# relays1.net
KiCad netlist of a schematic drawn in Altium Designer
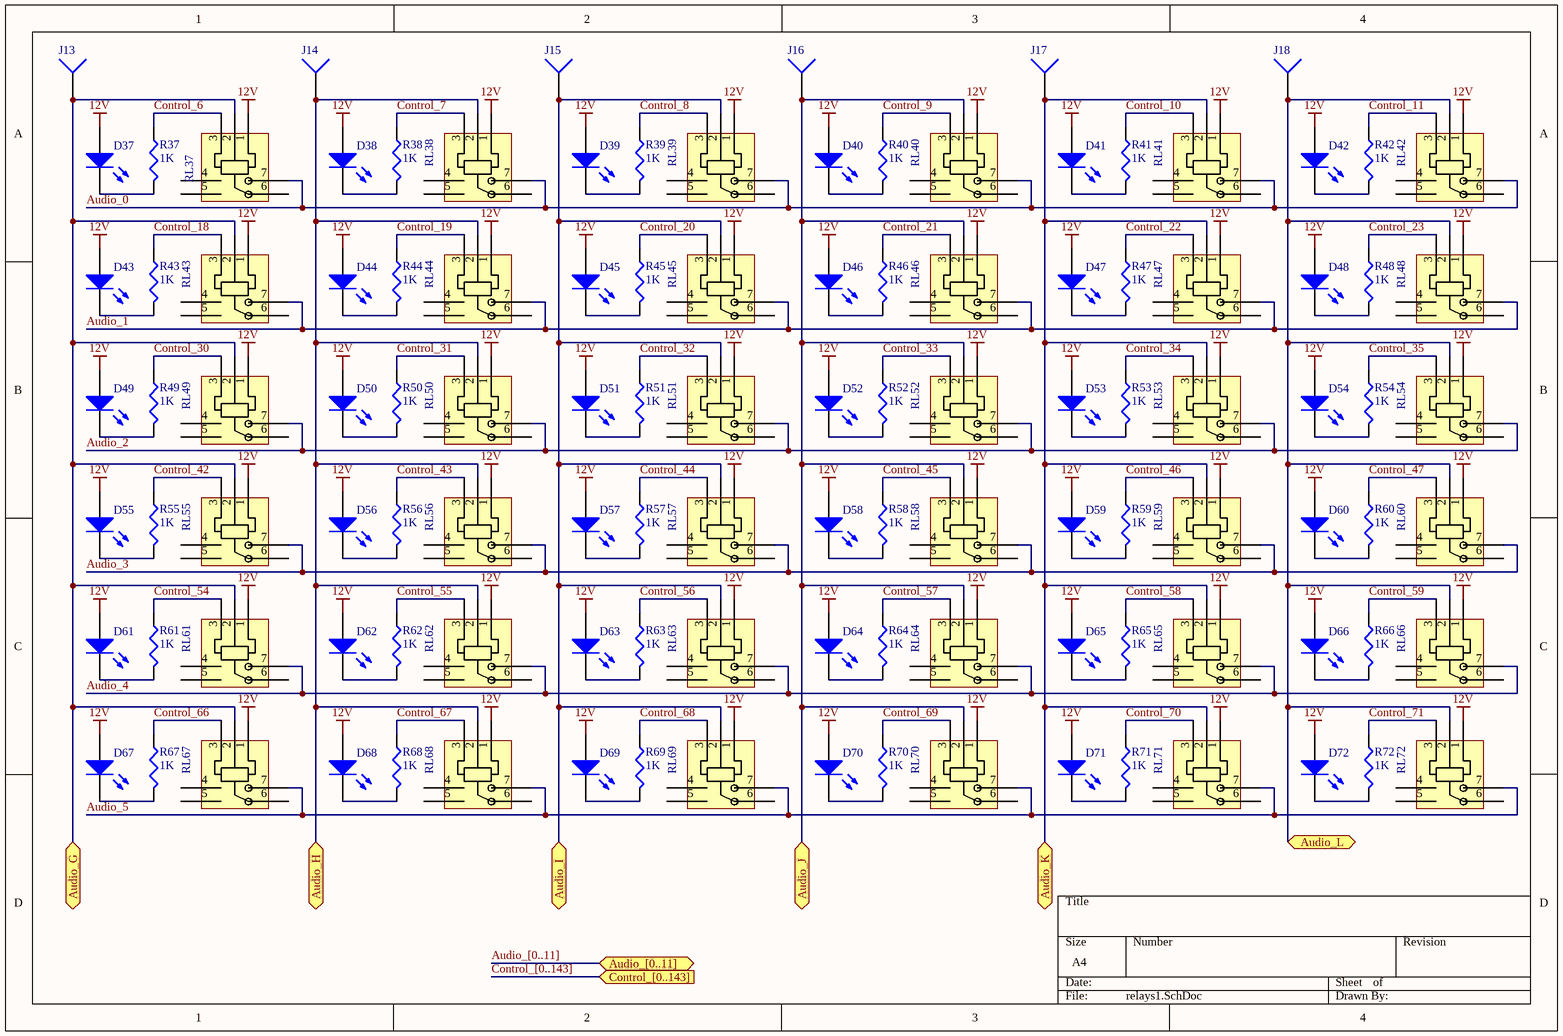
[diagram p0: relays1.SchDoc]

(export (version "E")
  (design (tool "Eeschema 10.0.6"))
  (components
    (comp (ref "D37")
      (value "LED0")
      (footprint "LED_round_5mm")
      (description "Typical INFRARED GaAs LED")
      (libsource (lib "Miscellaneous Devices") (part "LED0"))
    )
    (comp (ref "D38")
      (value "LED0")
      (footprint "LED_round_5mm")
      (description "Typical INFRARED GaAs LED")
      (libsource (lib "Miscellaneous Devices") (part "LED0"))
    )
    (comp (ref "D39")
      (value "LED0")
      (footprint "LED_round_5mm")
      (description "Typical INFRARED GaAs LED")
      (libsource (lib "Miscellaneous Devices") (part "LED0"))
    )
    (comp (ref "D40")
      (value "LED0")
      (footprint "LED_round_5mm")
      (description "Typical INFRARED GaAs LED")
      (libsource (lib "Miscellaneous Devices") (part "LED0"))
    )
    (comp (ref "D41")
      (value "LED0")
      (footprint "LED_round_5mm")
      (description "Typical INFRARED GaAs LED")
      (libsource (lib "Miscellaneous Devices") (part "LED0"))
    )
    (comp (ref "D42")
      (value "LED0")
      (footprint "LED_round_5mm")
      (description "Typical INFRARED GaAs LED")
      (libsource (lib "Miscellaneous Devices") (part "LED0"))
    )
    (comp (ref "D43")
      (value "LED0")
      (footprint "LED_round_5mm")
      (description "Typical INFRARED GaAs LED")
      (libsource (lib "Miscellaneous Devices") (part "LED0"))
    )
    (comp (ref "D44")
      (value "LED0")
      (footprint "LED_round_5mm")
      (description "Typical INFRARED GaAs LED")
      (libsource (lib "Miscellaneous Devices") (part "LED0"))
    )
    (comp (ref "D45")
      (value "LED0")
      (footprint "LED_round_5mm")
      (description "Typical INFRARED GaAs LED")
      (libsource (lib "Miscellaneous Devices") (part "LED0"))
    )
    (comp (ref "D46")
      (value "LED0")
      (footprint "LED_round_5mm")
      (description "Typical INFRARED GaAs LED")
      (libsource (lib "Miscellaneous Devices") (part "LED0"))
    )
    (comp (ref "D47")
      (value "LED0")
      (footprint "LED_round_5mm")
      (description "Typical INFRARED GaAs LED")
      (libsource (lib "Miscellaneous Devices") (part "LED0"))
    )
    (comp (ref "D48")
      (value "LED0")
      (footprint "LED_round_5mm")
      (description "Typical INFRARED GaAs LED")
      (libsource (lib "Miscellaneous Devices") (part "LED0"))
    )
    (comp (ref "D49")
      (value "LED0")
      (footprint "LED_round_5mm")
      (description "Typical INFRARED GaAs LED")
      (libsource (lib "Miscellaneous Devices") (part "LED0"))
    )
    (comp (ref "D50")
      (value "LED0")
      (footprint "LED_round_5mm")
      (description "Typical INFRARED GaAs LED")
      (libsource (lib "Miscellaneous Devices") (part "LED0"))
    )
    (comp (ref "D51")
      (value "LED0")
      (footprint "LED_round_5mm")
      (description "Typical INFRARED GaAs LED")
      (libsource (lib "Miscellaneous Devices") (part "LED0"))
    )
    (comp (ref "D52")
      (value "LED0")
      (footprint "LED_round_5mm")
      (description "Typical INFRARED GaAs LED")
      (libsource (lib "Miscellaneous Devices") (part "LED0"))
    )
    (comp (ref "D53")
      (value "LED0")
      (footprint "LED_round_5mm")
      (description "Typical INFRARED GaAs LED")
      (libsource (lib "Miscellaneous Devices") (part "LED0"))
    )
    (comp (ref "D54")
      (value "LED0")
      (footprint "LED_round_5mm")
      (description "Typical INFRARED GaAs LED")
      (libsource (lib "Miscellaneous Devices") (part "LED0"))
    )
    (comp (ref "D55")
      (value "LED0")
      (footprint "LED_round_5mm")
      (description "Typical INFRARED GaAs LED")
      (libsource (lib "Miscellaneous Devices") (part "LED0"))
    )
    (comp (ref "D56")
      (value "LED0")
      (footprint "LED_round_5mm")
      (description "Typical INFRARED GaAs LED")
      (libsource (lib "Miscellaneous Devices") (part "LED0"))
    )
    (comp (ref "D57")
      (value "LED0")
      (footprint "LED_round_5mm")
      (description "Typical INFRARED GaAs LED")
      (libsource (lib "Miscellaneous Devices") (part "LED0"))
    )
    (comp (ref "D58")
      (value "LED0")
      (footprint "LED_round_5mm")
      (description "Typical INFRARED GaAs LED")
      (libsource (lib "Miscellaneous Devices") (part "LED0"))
    )
    (comp (ref "D59")
      (value "LED0")
      (footprint "LED_round_5mm")
      (description "Typical INFRARED GaAs LED")
      (libsource (lib "Miscellaneous Devices") (part "LED0"))
    )
    (comp (ref "D60")
      (value "LED0")
      (footprint "LED_round_5mm")
      (description "Typical INFRARED GaAs LED")
      (libsource (lib "Miscellaneous Devices") (part "LED0"))
    )
    (comp (ref "D61")
      (value "LED0")
      (footprint "LED_round_5mm")
      (description "Typical INFRARED GaAs LED")
      (libsource (lib "Miscellaneous Devices") (part "LED0"))
    )
    (comp (ref "D62")
      (value "LED0")
      (footprint "LED_round_5mm")
      (description "Typical INFRARED GaAs LED")
      (libsource (lib "Miscellaneous Devices") (part "LED0"))
    )
    (comp (ref "D63")
      (value "LED0")
      (footprint "LED_round_5mm")
      (description "Typical INFRARED GaAs LED")
      (libsource (lib "Miscellaneous Devices") (part "LED0"))
    )
    (comp (ref "D64")
      (value "LED0")
      (footprint "LED_round_5mm")
      (description "Typical INFRARED GaAs LED")
      (libsource (lib "Miscellaneous Devices") (part "LED0"))
    )
    (comp (ref "D65")
      (value "LED0")
      (footprint "LED_round_5mm")
      (description "Typical INFRARED GaAs LED")
      (libsource (lib "Miscellaneous Devices") (part "LED0"))
    )
    (comp (ref "D66")
      (value "LED0")
      (footprint "LED_round_5mm")
      (description "Typical INFRARED GaAs LED")
      (libsource (lib "Miscellaneous Devices") (part "LED0"))
    )
    (comp (ref "D67")
      (value "LED0")
      (footprint "LED_round_5mm")
      (description "Typical INFRARED GaAs LED")
      (libsource (lib "Miscellaneous Devices") (part "LED0"))
    )
    (comp (ref "D68")
      (value "LED0")
      (footprint "LED_round_5mm")
      (description "Typical INFRARED GaAs LED")
      (libsource (lib "Miscellaneous Devices") (part "LED0"))
    )
    (comp (ref "D69")
      (value "LED0")
      (footprint "LED_round_5mm")
      (description "Typical INFRARED GaAs LED")
      (libsource (lib "Miscellaneous Devices") (part "LED0"))
    )
    (comp (ref "D70")
      (value "LED0")
      (footprint "LED_round_5mm")
      (description "Typical INFRARED GaAs LED")
      (libsource (lib "Miscellaneous Devices") (part "LED0"))
    )
    (comp (ref "D71")
      (value "LED0")
      (footprint "LED_round_5mm")
      (description "Typical INFRARED GaAs LED")
      (libsource (lib "Miscellaneous Devices") (part "LED0"))
    )
    (comp (ref "D72")
      (value "LED0")
      (footprint "LED_round_5mm")
      (description "Typical INFRARED GaAs LED")
      (libsource (lib "Miscellaneous Devices") (part "LED0"))
    )
    (comp (ref "J13")
      (value "Audio")
      (footprint "Conn_1_2x4")
      (description "Socket")
      (libsource (lib "Miscellaneous Connectors") (part "Socket"))
    )
    (comp (ref "J14")
      (value "Audio")
      (footprint "Conn_1_2x4")
      (description "Socket")
      (libsource (lib "Miscellaneous Connectors") (part "Socket"))
    )
    (comp (ref "J15")
      (value "Audio")
      (footprint "Conn_1_2x4")
      (description "Socket")
      (libsource (lib "Miscellaneous Connectors") (part "Socket"))
    )
    (comp (ref "J16")
      (value "Audio")
      (footprint "Conn_1_2x4")
      (description "Socket")
      (libsource (lib "Miscellaneous Connectors") (part "Socket"))
    )
    (comp (ref "J17")
      (value "Audio")
      (footprint "Conn_1_2x4")
      (description "Socket")
      (libsource (lib "Miscellaneous Connectors") (part "Socket"))
    )
    (comp (ref "J18")
      (value "Audio")
      (footprint "Conn_1_2x4")
      (description "Socket")
      (libsource (lib "Miscellaneous Connectors") (part "Socket"))
    )
    (comp (ref "R37")
      (value "1K")
      (footprint "J1-0603")
      (description "Resistor")
      (fields (field (name "Comment") "Res3"))
      (libsource (lib "Miscellaneous Devices") (part "Res3"))
    )
    (comp (ref "R38")
      (value "1K")
      (footprint "J1-0603")
      (description "Resistor")
      (fields (field (name "Comment") "Res3"))
      (libsource (lib "Miscellaneous Devices") (part "Res3"))
    )
    (comp (ref "R39")
      (value "1K")
      (footprint "J1-0603")
      (description "Resistor")
      (fields (field (name "Comment") "Res3"))
      (libsource (lib "Miscellaneous Devices") (part "Res3"))
    )
    (comp (ref "R40")
      (value "1K")
      (footprint "J1-0603")
      (description "Resistor")
      (fields (field (name "Comment") "Res3"))
      (libsource (lib "Miscellaneous Devices") (part "Res3"))
    )
    (comp (ref "R41")
      (value "1K")
      (footprint "J1-0603")
      (description "Resistor")
      (fields (field (name "Comment") "Res3"))
      (libsource (lib "Miscellaneous Devices") (part "Res3"))
    )
    (comp (ref "R42")
      (value "1K")
      (footprint "J1-0603")
      (description "Resistor")
      (fields (field (name "Comment") "Res3"))
      (libsource (lib "Miscellaneous Devices") (part "Res3"))
    )
    (comp (ref "R43")
      (value "1K")
      (footprint "J1-0603")
      (description "Resistor")
      (fields (field (name "Comment") "Res3"))
      (libsource (lib "Miscellaneous Devices") (part "Res3"))
    )
    (comp (ref "R44")
      (value "1K")
      (footprint "J1-0603")
      (description "Resistor")
      (fields (field (name "Comment") "Res3"))
      (libsource (lib "Miscellaneous Devices") (part "Res3"))
    )
    (comp (ref "R45")
      (value "1K")
      (footprint "J1-0603")
      (description "Resistor")
      (fields (field (name "Comment") "Res3"))
      (libsource (lib "Miscellaneous Devices") (part "Res3"))
    )
    (comp (ref "R46")
      (value "1K")
      (footprint "J1-0603")
      (description "Resistor")
      (fields (field (name "Comment") "Res3"))
      (libsource (lib "Miscellaneous Devices") (part "Res3"))
    )
    (comp (ref "R47")
      (value "1K")
      (footprint "J1-0603")
      (description "Resistor")
      (fields (field (name "Comment") "Res3"))
      (libsource (lib "Miscellaneous Devices") (part "Res3"))
    )
    (comp (ref "R48")
      (value "1K")
      (footprint "J1-0603")
      (description "Resistor")
      (fields (field (name "Comment") "Res3"))
      (libsource (lib "Miscellaneous Devices") (part "Res3"))
    )
    (comp (ref "R49")
      (value "1K")
      (footprint "J1-0603")
      (description "Resistor")
      (fields (field (name "Comment") "Res3"))
      (libsource (lib "Miscellaneous Devices") (part "Res3"))
    )
    (comp (ref "R50")
      (value "1K")
      (footprint "J1-0603")
      (description "Resistor")
      (fields (field (name "Comment") "Res3"))
      (libsource (lib "Miscellaneous Devices") (part "Res3"))
    )
    (comp (ref "R51")
      (value "1K")
      (footprint "J1-0603")
      (description "Resistor")
      (fields (field (name "Comment") "Res3"))
      (libsource (lib "Miscellaneous Devices") (part "Res3"))
    )
    (comp (ref "R52")
      (value "1K")
      (footprint "J1-0603")
      (description "Resistor")
      (fields (field (name "Comment") "Res3"))
      (libsource (lib "Miscellaneous Devices") (part "Res3"))
    )
    (comp (ref "R53")
      (value "1K")
      (footprint "J1-0603")
      (description "Resistor")
      (fields (field (name "Comment") "Res3"))
      (libsource (lib "Miscellaneous Devices") (part "Res3"))
    )
    (comp (ref "R54")
      (value "1K")
      (footprint "J1-0603")
      (description "Resistor")
      (fields (field (name "Comment") "Res3"))
      (libsource (lib "Miscellaneous Devices") (part "Res3"))
    )
    (comp (ref "R55")
      (value "1K")
      (footprint "J1-0603")
      (description "Resistor")
      (fields (field (name "Comment") "Res3"))
      (libsource (lib "Miscellaneous Devices") (part "Res3"))
    )
    (comp (ref "R56")
      (value "1K")
      (footprint "J1-0603")
      (description "Resistor")
      (fields (field (name "Comment") "Res3"))
      (libsource (lib "Miscellaneous Devices") (part "Res3"))
    )
    (comp (ref "R57")
      (value "1K")
      (footprint "J1-0603")
      (description "Resistor")
      (fields (field (name "Comment") "Res3"))
      (libsource (lib "Miscellaneous Devices") (part "Res3"))
    )
    (comp (ref "R58")
      (value "1K")
      (footprint "J1-0603")
      (description "Resistor")
      (fields (field (name "Comment") "Res3"))
      (libsource (lib "Miscellaneous Devices") (part "Res3"))
    )
    (comp (ref "R59")
      (value "1K")
      (footprint "J1-0603")
      (description "Resistor")
      (fields (field (name "Comment") "Res3"))
      (libsource (lib "Miscellaneous Devices") (part "Res3"))
    )
    (comp (ref "R60")
      (value "1K")
      (footprint "J1-0603")
      (description "Resistor")
      (fields (field (name "Comment") "Res3"))
      (libsource (lib "Miscellaneous Devices") (part "Res3"))
    )
    (comp (ref "R61")
      (value "1K")
      (footprint "J1-0603")
      (description "Resistor")
      (fields (field (name "Comment") "Res3"))
      (libsource (lib "Miscellaneous Devices") (part "Res3"))
    )
    (comp (ref "R62")
      (value "1K")
      (footprint "J1-0603")
      (description "Resistor")
      (fields (field (name "Comment") "Res3"))
      (libsource (lib "Miscellaneous Devices") (part "Res3"))
    )
    (comp (ref "R63")
      (value "1K")
      (footprint "J1-0603")
      (description "Resistor")
      (fields (field (name "Comment") "Res3"))
      (libsource (lib "Miscellaneous Devices") (part "Res3"))
    )
    (comp (ref "R64")
      (value "1K")
      (footprint "J1-0603")
      (description "Resistor")
      (fields (field (name "Comment") "Res3"))
      (libsource (lib "Miscellaneous Devices") (part "Res3"))
    )
    (comp (ref "R65")
      (value "1K")
      (footprint "J1-0603")
      (description "Resistor")
      (fields (field (name "Comment") "Res3"))
      (libsource (lib "Miscellaneous Devices") (part "Res3"))
    )
    (comp (ref "R66")
      (value "1K")
      (footprint "J1-0603")
      (description "Resistor")
      (fields (field (name "Comment") "Res3"))
      (libsource (lib "Miscellaneous Devices") (part "Res3"))
    )
    (comp (ref "R67")
      (value "1K")
      (footprint "J1-0603")
      (description "Resistor")
      (fields (field (name "Comment") "Res3"))
      (libsource (lib "Miscellaneous Devices") (part "Res3"))
    )
    (comp (ref "R68")
      (value "1K")
      (footprint "J1-0603")
      (description "Resistor")
      (fields (field (name "Comment") "Res3"))
      (libsource (lib "Miscellaneous Devices") (part "Res3"))
    )
    (comp (ref "R69")
      (value "1K")
      (footprint "J1-0603")
      (description "Resistor")
      (fields (field (name "Comment") "Res3"))
      (libsource (lib "Miscellaneous Devices") (part "Res3"))
    )
    (comp (ref "R70")
      (value "1K")
      (footprint "J1-0603")
      (description "Resistor")
      (fields (field (name "Comment") "Res3"))
      (libsource (lib "Miscellaneous Devices") (part "Res3"))
    )
    (comp (ref "R71")
      (value "1K")
      (footprint "J1-0603")
      (description "Resistor")
      (fields (field (name "Comment") "Res3"))
      (libsource (lib "Miscellaneous Devices") (part "Res3"))
    )
    (comp (ref "R72")
      (value "1K")
      (footprint "J1-0603")
      (description "Resistor")
      (fields (field (name "Comment") "Res3"))
      (libsource (lib "Miscellaneous Devices") (part "Res3"))
    )
    (comp (ref "RL37")
      (value "Relay")
      (footprint "Relay_FRA3")
      (description "Miniature power relay")
      (fields (field (name "PART NUMBER") "FRA3C-DC12"))
      (libsource (lib "tech-thing") (part "Relay_FRA3"))
    )
    (comp (ref "RL38")
      (value "Relay")
      (footprint "Relay_FRA3")
      (description "Miniature power relay")
      (fields (field (name "PART NUMBER") "FRA3C-DC12"))
      (libsource (lib "tech-thing") (part "Relay_FRA3"))
    )
    (comp (ref "RL39")
      (value "Relay")
      (footprint "Relay_FRA3")
      (description "Miniature power relay")
      (fields (field (name "PART NUMBER") "FRA3C-DC12"))
      (libsource (lib "tech-thing") (part "Relay_FRA3"))
    )
    (comp (ref "RL40")
      (value "Relay")
      (footprint "Relay_FRA3")
      (description "Miniature power relay")
      (fields (field (name "PART NUMBER") "FRA3C-DC12"))
      (libsource (lib "tech-thing") (part "Relay_FRA3"))
    )
    (comp (ref "RL41")
      (value "Relay")
      (footprint "Relay_FRA3")
      (description "Miniature power relay")
      (fields (field (name "PART NUMBER") "FRA3C-DC12"))
      (libsource (lib "tech-thing") (part "Relay_FRA3"))
    )
    (comp (ref "RL42")
      (value "Relay")
      (footprint "Relay_FRA3")
      (description "Miniature power relay")
      (fields (field (name "PART NUMBER") "FRA3C-DC12"))
      (libsource (lib "tech-thing") (part "Relay_FRA3"))
    )
    (comp (ref "RL43")
      (value "Relay")
      (footprint "Relay_FRA3")
      (description "Miniature power relay")
      (fields (field (name "PART NUMBER") "FRA3C-DC12"))
      (libsource (lib "tech-thing") (part "Relay_FRA3"))
    )
    (comp (ref "RL44")
      (value "Relay")
      (footprint "Relay_FRA3")
      (description "Miniature power relay")
      (fields (field (name "PART NUMBER") "FRA3C-DC12"))
      (libsource (lib "tech-thing") (part "Relay_FRA3"))
    )
    (comp (ref "RL45")
      (value "Relay")
      (footprint "Relay_FRA3")
      (description "Miniature power relay")
      (fields (field (name "PART NUMBER") "FRA3C-DC12"))
      (libsource (lib "tech-thing") (part "Relay_FRA3"))
    )
    (comp (ref "RL46")
      (value "Relay")
      (footprint "Relay_FRA3")
      (description "Miniature power relay")
      (fields (field (name "PART NUMBER") "FRA3C-DC12"))
      (libsource (lib "tech-thing") (part "Relay_FRA3"))
    )
    (comp (ref "RL47")
      (value "Relay")
      (footprint "Relay_FRA3")
      (description "Miniature power relay")
      (fields (field (name "PART NUMBER") "FRA3C-DC12"))
      (libsource (lib "tech-thing") (part "Relay_FRA3"))
    )
    (comp (ref "RL48")
      (value "Relay")
      (footprint "Relay_FRA3")
      (description "Miniature power relay")
      (fields (field (name "PART NUMBER") "FRA3C-DC12"))
      (libsource (lib "tech-thing") (part "Relay_FRA3"))
    )
    (comp (ref "RL49")
      (value "Relay")
      (footprint "Relay_FRA3")
      (description "Miniature power relay")
      (fields (field (name "PART NUMBER") "FRA3C-DC12"))
      (libsource (lib "tech-thing") (part "Relay_FRA3"))
    )
    (comp (ref "RL50")
      (value "Relay")
      (footprint "Relay_FRA3")
      (description "Miniature power relay")
      (fields (field (name "PART NUMBER") "FRA3C-DC12"))
      (libsource (lib "tech-thing") (part "Relay_FRA3"))
    )
    (comp (ref "RL51")
      (value "Relay")
      (footprint "Relay_FRA3")
      (description "Miniature power relay")
      (fields (field (name "PART NUMBER") "FRA3C-DC12"))
      (libsource (lib "tech-thing") (part "Relay_FRA3"))
    )
    (comp (ref "RL52")
      (value "Relay")
      (footprint "Relay_FRA3")
      (description "Miniature power relay")
      (fields (field (name "PART NUMBER") "FRA3C-DC12"))
      (libsource (lib "tech-thing") (part "Relay_FRA3"))
    )
    (comp (ref "RL53")
      (value "Relay")
      (footprint "Relay_FRA3")
      (description "Miniature power relay")
      (fields (field (name "PART NUMBER") "FRA3C-DC12"))
      (libsource (lib "tech-thing") (part "Relay_FRA3"))
    )
    (comp (ref "RL54")
      (value "Relay")
      (footprint "Relay_FRA3")
      (description "Miniature power relay")
      (fields (field (name "PART NUMBER") "FRA3C-DC12"))
      (libsource (lib "tech-thing") (part "Relay_FRA3"))
    )
    (comp (ref "RL55")
      (value "Relay")
      (footprint "Relay_FRA3")
      (description "Miniature power relay")
      (fields (field (name "PART NUMBER") "FRA3C-DC12"))
      (libsource (lib "tech-thing") (part "Relay_FRA3"))
    )
    (comp (ref "RL56")
      (value "Relay")
      (footprint "Relay_FRA3")
      (description "Miniature power relay")
      (fields (field (name "PART NUMBER") "FRA3C-DC12"))
      (libsource (lib "tech-thing") (part "Relay_FRA3"))
    )
    (comp (ref "RL57")
      (value "Relay")
      (footprint "Relay_FRA3")
      (description "Miniature power relay")
      (fields (field (name "PART NUMBER") "FRA3C-DC12"))
      (libsource (lib "tech-thing") (part "Relay_FRA3"))
    )
    (comp (ref "RL58")
      (value "Relay")
      (footprint "Relay_FRA3")
      (description "Miniature power relay")
      (fields (field (name "PART NUMBER") "FRA3C-DC12"))
      (libsource (lib "tech-thing") (part "Relay_FRA3"))
    )
    (comp (ref "RL59")
      (value "Relay")
      (footprint "Relay_FRA3")
      (description "Miniature power relay")
      (fields (field (name "PART NUMBER") "FRA3C-DC12"))
      (libsource (lib "tech-thing") (part "Relay_FRA3"))
    )
    (comp (ref "RL60")
      (value "Relay")
      (footprint "Relay_FRA3")
      (description "Miniature power relay")
      (fields (field (name "PART NUMBER") "FRA3C-DC12"))
      (libsource (lib "tech-thing") (part "Relay_FRA3"))
    )
    (comp (ref "RL61")
      (value "Relay")
      (footprint "Relay_FRA3")
      (description "Miniature power relay")
      (fields (field (name "PART NUMBER") "FRA3C-DC12"))
      (libsource (lib "tech-thing") (part "Relay_FRA3"))
    )
    (comp (ref "RL62")
      (value "Relay")
      (footprint "Relay_FRA3")
      (description "Miniature power relay")
      (fields (field (name "PART NUMBER") "FRA3C-DC12"))
      (libsource (lib "tech-thing") (part "Relay_FRA3"))
    )
    (comp (ref "RL63")
      (value "Relay")
      (footprint "Relay_FRA3")
      (description "Miniature power relay")
      (fields (field (name "PART NUMBER") "FRA3C-DC12"))
      (libsource (lib "tech-thing") (part "Relay_FRA3"))
    )
    (comp (ref "RL64")
      (value "Relay")
      (footprint "Relay_FRA3")
      (description "Miniature power relay")
      (fields (field (name "PART NUMBER") "FRA3C-DC12"))
      (libsource (lib "tech-thing") (part "Relay_FRA3"))
    )
    (comp (ref "RL65")
      (value "Relay")
      (footprint "Relay_FRA3")
      (description "Miniature power relay")
      (fields (field (name "PART NUMBER") "FRA3C-DC12"))
      (libsource (lib "tech-thing") (part "Relay_FRA3"))
    )
    (comp (ref "RL66")
      (value "Relay")
      (footprint "Relay_FRA3")
      (description "Miniature power relay")
      (fields (field (name "PART NUMBER") "FRA3C-DC12"))
      (libsource (lib "tech-thing") (part "Relay_FRA3"))
    )
    (comp (ref "RL67")
      (value "Relay")
      (footprint "Relay_FRA3")
      (description "Miniature power relay")
      (fields (field (name "PART NUMBER") "FRA3C-DC12"))
      (libsource (lib "tech-thing") (part "Relay_FRA3"))
    )
    (comp (ref "RL68")
      (value "Relay")
      (footprint "Relay_FRA3")
      (description "Miniature power relay")
      (fields (field (name "PART NUMBER") "FRA3C-DC12"))
      (libsource (lib "tech-thing") (part "Relay_FRA3"))
    )
    (comp (ref "RL69")
      (value "Relay")
      (footprint "Relay_FRA3")
      (description "Miniature power relay")
      (fields (field (name "PART NUMBER") "FRA3C-DC12"))
      (libsource (lib "tech-thing") (part "Relay_FRA3"))
    )
    (comp (ref "RL70")
      (value "Relay")
      (footprint "Relay_FRA3")
      (description "Miniature power relay")
      (fields (field (name "PART NUMBER") "FRA3C-DC12"))
      (libsource (lib "tech-thing") (part "Relay_FRA3"))
    )
    (comp (ref "RL71")
      (value "Relay")
      (footprint "Relay_FRA3")
      (description "Miniature power relay")
      (fields (field (name "PART NUMBER") "FRA3C-DC12"))
      (libsource (lib "tech-thing") (part "Relay_FRA3"))
    )
    (comp (ref "RL72")
      (value "Relay")
      (footprint "Relay_FRA3")
      (description "Miniature power relay")
      (fields (field (name "PART NUMBER") "FRA3C-DC12"))
      (libsource (lib "tech-thing") (part "Relay_FRA3"))
    )
  )
  (nets
    (net (code "115") (name "/Audio_0") (class "Default")
      (node (ref "RL37") (pin "7") (pintype "passive"))
      (node (ref "RL38") (pin "7") (pintype "passive"))
      (node (ref "RL39") (pin "7") (pintype "passive"))
      (node (ref "RL40") (pin "7") (pintype "passive"))
      (node (ref "RL41") (pin "7") (pintype "passive"))
      (node (ref "RL42") (pin "7") (pintype "passive"))
    )
    (net (code "116") (name "/Audio_1") (class "Default")
      (node (ref "RL43") (pin "7") (pintype "passive"))
      (node (ref "RL44") (pin "7") (pintype "passive"))
      (node (ref "RL45") (pin "7") (pintype "passive"))
      (node (ref "RL46") (pin "7") (pintype "passive"))
      (node (ref "RL47") (pin "7") (pintype "passive"))
      (node (ref "RL48") (pin "7") (pintype "passive"))
    )
    (net (code "117") (name "/Audio_2") (class "Default")
      (node (ref "RL49") (pin "7") (pintype "passive"))
      (node (ref "RL50") (pin "7") (pintype "passive"))
      (node (ref "RL51") (pin "7") (pintype "passive"))
      (node (ref "RL52") (pin "7") (pintype "passive"))
      (node (ref "RL53") (pin "7") (pintype "passive"))
      (node (ref "RL54") (pin "7") (pintype "passive"))
    )
    (net (code "118") (name "/Audio_3") (class "Default")
      (node (ref "RL55") (pin "7") (pintype "passive"))
      (node (ref "RL56") (pin "7") (pintype "passive"))
      (node (ref "RL57") (pin "7") (pintype "passive"))
      (node (ref "RL58") (pin "7") (pintype "passive"))
      (node (ref "RL59") (pin "7") (pintype "passive"))
      (node (ref "RL60") (pin "7") (pintype "passive"))
    )
    (net (code "119") (name "/Audio_4") (class "Default")
      (node (ref "RL61") (pin "7") (pintype "passive"))
      (node (ref "RL62") (pin "7") (pintype "passive"))
      (node (ref "RL63") (pin "7") (pintype "passive"))
      (node (ref "RL64") (pin "7") (pintype "passive"))
      (node (ref "RL65") (pin "7") (pintype "passive"))
      (node (ref "RL66") (pin "7") (pintype "passive"))
    )
    (net (code "120") (name "/Audio_5") (class "Default")
      (node (ref "RL67") (pin "7") (pintype "passive"))
      (node (ref "RL68") (pin "7") (pintype "passive"))
      (node (ref "RL69") (pin "7") (pintype "passive"))
      (node (ref "RL70") (pin "7") (pintype "passive"))
      (node (ref "RL71") (pin "7") (pintype "passive"))
      (node (ref "RL72") (pin "7") (pintype "passive"))
    )
    (net (code "121") (name "/Audio_G") (class "Default")
      (node (ref "J13") (pin "1") (pinfunction "1_1") (pintype "passive"))
      (node (ref "RL37") (pin "2") (pintype "passive"))
      (node (ref "RL43") (pin "2") (pintype "passive"))
      (node (ref "RL49") (pin "2") (pintype "passive"))
      (node (ref "RL55") (pin "2") (pintype "passive"))
      (node (ref "RL61") (pin "2") (pintype "passive"))
      (node (ref "RL67") (pin "2") (pintype "passive"))
    )
    (net (code "122") (name "/Audio_H") (class "Default")
      (node (ref "J14") (pin "1") (pinfunction "1_1") (pintype "passive"))
      (node (ref "RL38") (pin "2") (pintype "passive"))
      (node (ref "RL44") (pin "2") (pintype "passive"))
      (node (ref "RL50") (pin "2") (pintype "passive"))
      (node (ref "RL56") (pin "2") (pintype "passive"))
      (node (ref "RL62") (pin "2") (pintype "passive"))
      (node (ref "RL68") (pin "2") (pintype "passive"))
    )
    (net (code "123") (name "/Audio_I") (class "Default")
      (node (ref "J15") (pin "1") (pinfunction "1_1") (pintype "passive"))
      (node (ref "RL39") (pin "2") (pintype "passive"))
      (node (ref "RL45") (pin "2") (pintype "passive"))
      (node (ref "RL51") (pin "2") (pintype "passive"))
      (node (ref "RL57") (pin "2") (pintype "passive"))
      (node (ref "RL63") (pin "2") (pintype "passive"))
      (node (ref "RL69") (pin "2") (pintype "passive"))
    )
    (net (code "124") (name "/Audio_J") (class "Default")
      (node (ref "J16") (pin "1") (pinfunction "1_1") (pintype "passive"))
      (node (ref "RL40") (pin "2") (pintype "passive"))
      (node (ref "RL46") (pin "2") (pintype "passive"))
      (node (ref "RL52") (pin "2") (pintype "passive"))
      (node (ref "RL58") (pin "2") (pintype "passive"))
      (node (ref "RL64") (pin "2") (pintype "passive"))
      (node (ref "RL70") (pin "2") (pintype "passive"))
    )
    (net (code "125") (name "/Audio_K") (class "Default")
      (node (ref "J17") (pin "1") (pinfunction "1_1") (pintype "passive"))
      (node (ref "RL41") (pin "2") (pintype "passive"))
      (node (ref "RL47") (pin "2") (pintype "passive"))
      (node (ref "RL53") (pin "2") (pintype "passive"))
      (node (ref "RL59") (pin "2") (pintype "passive"))
      (node (ref "RL65") (pin "2") (pintype "passive"))
      (node (ref "RL71") (pin "2") (pintype "passive"))
    )
    (net (code "126") (name "/Audio_L") (class "Default")
      (node (ref "J18") (pin "1") (pinfunction "1_1") (pintype "passive"))
      (node (ref "RL42") (pin "2") (pintype "passive"))
      (node (ref "RL48") (pin "2") (pintype "passive"))
      (node (ref "RL54") (pin "2") (pintype "passive"))
      (node (ref "RL60") (pin "2") (pintype "passive"))
      (node (ref "RL66") (pin "2") (pintype "passive"))
      (node (ref "RL72") (pin "2") (pintype "passive"))
    )
    (net (code "128") (name "/Control_6") (class "Default")
      (node (ref "R37") (pin "1") (pinfunction "1_1") (pintype "passive"))
      (node (ref "RL37") (pin "3") (pintype "passive"))
    )
    (net (code "129") (name "/Control_7") (class "Default")
      (node (ref "R38") (pin "1") (pinfunction "1_1") (pintype "passive"))
      (node (ref "RL38") (pin "3") (pintype "passive"))
    )
    (net (code "130") (name "/Control_8") (class "Default")
      (node (ref "R39") (pin "1") (pinfunction "1_1") (pintype "passive"))
      (node (ref "RL39") (pin "3") (pintype "passive"))
    )
    (net (code "131") (name "/Control_9") (class "Default")
      (node (ref "R40") (pin "1") (pinfunction "1_1") (pintype "passive"))
      (node (ref "RL40") (pin "3") (pintype "passive"))
    )
    (net (code "132") (name "/Control_10") (class "Default")
      (node (ref "R41") (pin "1") (pinfunction "1_1") (pintype "passive"))
      (node (ref "RL41") (pin "3") (pintype "passive"))
    )
    (net (code "133") (name "/Control_11") (class "Default")
      (node (ref "R42") (pin "1") (pinfunction "1_1") (pintype "passive"))
      (node (ref "RL42") (pin "3") (pintype "passive"))
    )
    (net (code "134") (name "/Control_18") (class "Default")
      (node (ref "R43") (pin "1") (pinfunction "1_1") (pintype "passive"))
      (node (ref "RL43") (pin "3") (pintype "passive"))
    )
    (net (code "135") (name "/Control_19") (class "Default")
      (node (ref "R44") (pin "1") (pinfunction "1_1") (pintype "passive"))
      (node (ref "RL44") (pin "3") (pintype "passive"))
    )
    (net (code "136") (name "/Control_20") (class "Default")
      (node (ref "R45") (pin "1") (pinfunction "1_1") (pintype "passive"))
      (node (ref "RL45") (pin "3") (pintype "passive"))
    )
    (net (code "137") (name "/Control_21") (class "Default")
      (node (ref "R46") (pin "1") (pinfunction "1_1") (pintype "passive"))
      (node (ref "RL46") (pin "3") (pintype "passive"))
    )
    (net (code "138") (name "/Control_22") (class "Default")
      (node (ref "R47") (pin "1") (pinfunction "1_1") (pintype "passive"))
      (node (ref "RL47") (pin "3") (pintype "passive"))
    )
    (net (code "139") (name "/Control_23") (class "Default")
      (node (ref "R48") (pin "1") (pinfunction "1_1") (pintype "passive"))
      (node (ref "RL48") (pin "3") (pintype "passive"))
    )
    (net (code "140") (name "/Control_30") (class "Default")
      (node (ref "R49") (pin "1") (pinfunction "1_1") (pintype "passive"))
      (node (ref "RL49") (pin "3") (pintype "passive"))
    )
    (net (code "141") (name "/Control_31") (class "Default")
      (node (ref "R50") (pin "1") (pinfunction "1_1") (pintype "passive"))
      (node (ref "RL50") (pin "3") (pintype "passive"))
    )
    (net (code "142") (name "/Control_32") (class "Default")
      (node (ref "R51") (pin "1") (pinfunction "1_1") (pintype "passive"))
      (node (ref "RL51") (pin "3") (pintype "passive"))
    )
    (net (code "143") (name "/Control_33") (class "Default")
      (node (ref "R52") (pin "1") (pinfunction "1_1") (pintype "passive"))
      (node (ref "RL52") (pin "3") (pintype "passive"))
    )
    (net (code "144") (name "/Control_34") (class "Default")
      (node (ref "R53") (pin "1") (pinfunction "1_1") (pintype "passive"))
      (node (ref "RL53") (pin "3") (pintype "passive"))
    )
    (net (code "145") (name "/Control_35") (class "Default")
      (node (ref "R54") (pin "1") (pinfunction "1_1") (pintype "passive"))
      (node (ref "RL54") (pin "3") (pintype "passive"))
    )
    (net (code "146") (name "/Control_42") (class "Default")
      (node (ref "R55") (pin "1") (pinfunction "1_1") (pintype "passive"))
      (node (ref "RL55") (pin "3") (pintype "passive"))
    )
    (net (code "147") (name "/Control_43") (class "Default")
      (node (ref "R56") (pin "1") (pinfunction "1_1") (pintype "passive"))
      (node (ref "RL56") (pin "3") (pintype "passive"))
    )
    (net (code "148") (name "/Control_44") (class "Default")
      (node (ref "R57") (pin "1") (pinfunction "1_1") (pintype "passive"))
      (node (ref "RL57") (pin "3") (pintype "passive"))
    )
    (net (code "149") (name "/Control_45") (class "Default")
      (node (ref "R58") (pin "1") (pinfunction "1_1") (pintype "passive"))
      (node (ref "RL58") (pin "3") (pintype "passive"))
    )
    (net (code "150") (name "/Control_46") (class "Default")
      (node (ref "R59") (pin "1") (pinfunction "1_1") (pintype "passive"))
      (node (ref "RL59") (pin "3") (pintype "passive"))
    )
    (net (code "151") (name "/Control_47") (class "Default")
      (node (ref "R60") (pin "1") (pinfunction "1_1") (pintype "passive"))
      (node (ref "RL60") (pin "3") (pintype "passive"))
    )
    (net (code "152") (name "/Control_54") (class "Default")
      (node (ref "R61") (pin "1") (pinfunction "1_1") (pintype "passive"))
      (node (ref "RL61") (pin "3") (pintype "passive"))
    )
    (net (code "153") (name "/Control_55") (class "Default")
      (node (ref "R62") (pin "1") (pinfunction "1_1") (pintype "passive"))
      (node (ref "RL62") (pin "3") (pintype "passive"))
    )
    (net (code "154") (name "/Control_56") (class "Default")
      (node (ref "R63") (pin "1") (pinfunction "1_1") (pintype "passive"))
      (node (ref "RL63") (pin "3") (pintype "passive"))
    )
    (net (code "155") (name "/Control_57") (class "Default")
      (node (ref "R64") (pin "1") (pinfunction "1_1") (pintype "passive"))
      (node (ref "RL64") (pin "3") (pintype "passive"))
    )
    (net (code "156") (name "/Control_58") (class "Default")
      (node (ref "R65") (pin "1") (pinfunction "1_1") (pintype "passive"))
      (node (ref "RL65") (pin "3") (pintype "passive"))
    )
    (net (code "157") (name "/Control_59") (class "Default")
      (node (ref "R66") (pin "1") (pinfunction "1_1") (pintype "passive"))
      (node (ref "RL66") (pin "3") (pintype "passive"))
    )
    (net (code "158") (name "/Control_66") (class "Default")
      (node (ref "R67") (pin "1") (pinfunction "1_1") (pintype "passive"))
      (node (ref "RL67") (pin "3") (pintype "passive"))
    )
    (net (code "159") (name "/Control_67") (class "Default")
      (node (ref "R68") (pin "1") (pinfunction "1_1") (pintype "passive"))
      (node (ref "RL68") (pin "3") (pintype "passive"))
    )
    (net (code "160") (name "/Control_68") (class "Default")
      (node (ref "R69") (pin "1") (pinfunction "1_1") (pintype "passive"))
      (node (ref "RL69") (pin "3") (pintype "passive"))
    )
    (net (code "161") (name "/Control_69") (class "Default")
      (node (ref "R70") (pin "1") (pinfunction "1_1") (pintype "passive"))
      (node (ref "RL70") (pin "3") (pintype "passive"))
    )
    (net (code "162") (name "/Control_70") (class "Default")
      (node (ref "R71") (pin "1") (pinfunction "1_1") (pintype "passive"))
      (node (ref "RL71") (pin "3") (pintype "passive"))
    )
    (net (code "163") (name "/Control_71") (class "Default")
      (node (ref "R72") (pin "1") (pinfunction "1_1") (pintype "passive"))
      (node (ref "RL72") (pin "3") (pintype "passive"))
    )
    (net (code "165") (name "12V") (class "Default")
      (node (ref "D37") (pin "1") (pinfunction "A_1") (pintype "passive"))
      (node (ref "D38") (pin "1") (pinfunction "A_1") (pintype "passive"))
      (node (ref "D39") (pin "1") (pinfunction "A_1") (pintype "passive"))
      (node (ref "D40") (pin "1") (pinfunction "A_1") (pintype "passive"))
      (node (ref "D41") (pin "1") (pinfunction "A_1") (pintype "passive"))
      (node (ref "D42") (pin "1") (pinfunction "A_1") (pintype "passive"))
      (node (ref "D43") (pin "1") (pinfunction "A_1") (pintype "passive"))
      (node (ref "D44") (pin "1") (pinfunction "A_1") (pintype "passive"))
      (node (ref "D45") (pin "1") (pinfunction "A_1") (pintype "passive"))
      (node (ref "D46") (pin "1") (pinfunction "A_1") (pintype "passive"))
      (node (ref "D47") (pin "1") (pinfunction "A_1") (pintype "passive"))
      (node (ref "D48") (pin "1") (pinfunction "A_1") (pintype "passive"))
      (node (ref "D49") (pin "1") (pinfunction "A_1") (pintype "passive"))
      (node (ref "D50") (pin "1") (pinfunction "A_1") (pintype "passive"))
      (node (ref "D51") (pin "1") (pinfunction "A_1") (pintype "passive"))
      (node (ref "D52") (pin "1") (pinfunction "A_1") (pintype "passive"))
      (node (ref "D53") (pin "1") (pinfunction "A_1") (pintype "passive"))
      (node (ref "D54") (pin "1") (pinfunction "A_1") (pintype "passive"))
      (node (ref "D55") (pin "1") (pinfunction "A_1") (pintype "passive"))
      (node (ref "D56") (pin "1") (pinfunction "A_1") (pintype "passive"))
      (node (ref "D57") (pin "1") (pinfunction "A_1") (pintype "passive"))
      (node (ref "D58") (pin "1") (pinfunction "A_1") (pintype "passive"))
      (node (ref "D59") (pin "1") (pinfunction "A_1") (pintype "passive"))
      (node (ref "D60") (pin "1") (pinfunction "A_1") (pintype "passive"))
      (node (ref "D61") (pin "1") (pinfunction "A_1") (pintype "passive"))
      (node (ref "D62") (pin "1") (pinfunction "A_1") (pintype "passive"))
      (node (ref "D63") (pin "1") (pinfunction "A_1") (pintype "passive"))
      (node (ref "D64") (pin "1") (pinfunction "A_1") (pintype "passive"))
      (node (ref "D65") (pin "1") (pinfunction "A_1") (pintype "passive"))
      (node (ref "D66") (pin "1") (pinfunction "A_1") (pintype "passive"))
      (node (ref "D67") (pin "1") (pinfunction "A_1") (pintype "passive"))
      (node (ref "D68") (pin "1") (pinfunction "A_1") (pintype "passive"))
      (node (ref "D69") (pin "1") (pinfunction "A_1") (pintype "passive"))
      (node (ref "D70") (pin "1") (pinfunction "A_1") (pintype "passive"))
      (node (ref "D71") (pin "1") (pinfunction "A_1") (pintype "passive"))
      (node (ref "D72") (pin "1") (pinfunction "A_1") (pintype "passive"))
      (node (ref "RL37") (pin "1") (pintype "passive"))
      (node (ref "RL38") (pin "1") (pintype "passive"))
      (node (ref "RL39") (pin "1") (pintype "passive"))
      (node (ref "RL40") (pin "1") (pintype "passive"))
      (node (ref "RL41") (pin "1") (pintype "passive"))
      (node (ref "RL42") (pin "1") (pintype "passive"))
      (node (ref "RL43") (pin "1") (pintype "passive"))
      (node (ref "RL44") (pin "1") (pintype "passive"))
      (node (ref "RL45") (pin "1") (pintype "passive"))
      (node (ref "RL46") (pin "1") (pintype "passive"))
      (node (ref "RL47") (pin "1") (pintype "passive"))
      (node (ref "RL48") (pin "1") (pintype "passive"))
      (node (ref "RL49") (pin "1") (pintype "passive"))
      (node (ref "RL50") (pin "1") (pintype "passive"))
      (node (ref "RL51") (pin "1") (pintype "passive"))
      (node (ref "RL52") (pin "1") (pintype "passive"))
      (node (ref "RL53") (pin "1") (pintype "passive"))
      (node (ref "RL54") (pin "1") (pintype "passive"))
      (node (ref "RL55") (pin "1") (pintype "passive"))
      (node (ref "RL56") (pin "1") (pintype "passive"))
      (node (ref "RL57") (pin "1") (pintype "passive"))
      (node (ref "RL58") (pin "1") (pintype "passive"))
      (node (ref "RL59") (pin "1") (pintype "passive"))
      (node (ref "RL60") (pin "1") (pintype "passive"))
      (node (ref "RL61") (pin "1") (pintype "passive"))
      (node (ref "RL62") (pin "1") (pintype "passive"))
      (node (ref "RL63") (pin "1") (pintype "passive"))
      (node (ref "RL64") (pin "1") (pintype "passive"))
      (node (ref "RL65") (pin "1") (pintype "passive"))
      (node (ref "RL66") (pin "1") (pintype "passive"))
      (node (ref "RL67") (pin "1") (pintype "passive"))
      (node (ref "RL68") (pin "1") (pintype "passive"))
      (node (ref "RL69") (pin "1") (pintype "passive"))
      (node (ref "RL70") (pin "1") (pintype "passive"))
      (node (ref "RL71") (pin "1") (pintype "passive"))
      (node (ref "RL72") (pin "1") (pintype "passive"))
    )
    (net (code "166") (name "Net-(D37-K)") (class "Default")
      (node (ref "D37") (pin "2") (pinfunction "K_2") (pintype "passive"))
      (node (ref "R37") (pin "2") (pinfunction "2_2") (pintype "passive"))
    )
    (net (code "167") (name "Net-(D38-K)") (class "Default")
      (node (ref "D38") (pin "2") (pinfunction "K_2") (pintype "passive"))
      (node (ref "R38") (pin "2") (pinfunction "2_2") (pintype "passive"))
    )
    (net (code "168") (name "Net-(D39-K)") (class "Default")
      (node (ref "D39") (pin "2") (pinfunction "K_2") (pintype "passive"))
      (node (ref "R39") (pin "2") (pinfunction "2_2") (pintype "passive"))
    )
    (net (code "169") (name "Net-(D40-K)") (class "Default")
      (node (ref "D40") (pin "2") (pinfunction "K_2") (pintype "passive"))
      (node (ref "R40") (pin "2") (pinfunction "2_2") (pintype "passive"))
    )
    (net (code "170") (name "Net-(D41-K)") (class "Default")
      (node (ref "D41") (pin "2") (pinfunction "K_2") (pintype "passive"))
      (node (ref "R41") (pin "2") (pinfunction "2_2") (pintype "passive"))
    )
    (net (code "171") (name "Net-(D42-K)") (class "Default")
      (node (ref "D42") (pin "2") (pinfunction "K_2") (pintype "passive"))
      (node (ref "R42") (pin "2") (pinfunction "2_2") (pintype "passive"))
    )
    (net (code "172") (name "Net-(D43-K)") (class "Default")
      (node (ref "D43") (pin "2") (pinfunction "K_2") (pintype "passive"))
      (node (ref "R43") (pin "2") (pinfunction "2_2") (pintype "passive"))
    )
    (net (code "173") (name "Net-(D44-K)") (class "Default")
      (node (ref "D44") (pin "2") (pinfunction "K_2") (pintype "passive"))
      (node (ref "R44") (pin "2") (pinfunction "2_2") (pintype "passive"))
    )
    (net (code "174") (name "Net-(D45-K)") (class "Default")
      (node (ref "D45") (pin "2") (pinfunction "K_2") (pintype "passive"))
      (node (ref "R45") (pin "2") (pinfunction "2_2") (pintype "passive"))
    )
    (net (code "175") (name "Net-(D46-K)") (class "Default")
      (node (ref "D46") (pin "2") (pinfunction "K_2") (pintype "passive"))
      (node (ref "R46") (pin "2") (pinfunction "2_2") (pintype "passive"))
    )
    (net (code "176") (name "Net-(D47-K)") (class "Default")
      (node (ref "D47") (pin "2") (pinfunction "K_2") (pintype "passive"))
      (node (ref "R47") (pin "2") (pinfunction "2_2") (pintype "passive"))
    )
    (net (code "177") (name "Net-(D48-K)") (class "Default")
      (node (ref "D48") (pin "2") (pinfunction "K_2") (pintype "passive"))
      (node (ref "R48") (pin "2") (pinfunction "2_2") (pintype "passive"))
    )
    (net (code "178") (name "Net-(D49-K)") (class "Default")
      (node (ref "D49") (pin "2") (pinfunction "K_2") (pintype "passive"))
      (node (ref "R49") (pin "2") (pinfunction "2_2") (pintype "passive"))
    )
    (net (code "179") (name "Net-(D50-K)") (class "Default")
      (node (ref "D50") (pin "2") (pinfunction "K_2") (pintype "passive"))
      (node (ref "R50") (pin "2") (pinfunction "2_2") (pintype "passive"))
    )
    (net (code "180") (name "Net-(D51-K)") (class "Default")
      (node (ref "D51") (pin "2") (pinfunction "K_2") (pintype "passive"))
      (node (ref "R51") (pin "2") (pinfunction "2_2") (pintype "passive"))
    )
    (net (code "181") (name "Net-(D52-K)") (class "Default")
      (node (ref "D52") (pin "2") (pinfunction "K_2") (pintype "passive"))
      (node (ref "R52") (pin "2") (pinfunction "2_2") (pintype "passive"))
    )
    (net (code "182") (name "Net-(D53-K)") (class "Default")
      (node (ref "D53") (pin "2") (pinfunction "K_2") (pintype "passive"))
      (node (ref "R53") (pin "2") (pinfunction "2_2") (pintype "passive"))
    )
    (net (code "183") (name "Net-(D54-K)") (class "Default")
      (node (ref "D54") (pin "2") (pinfunction "K_2") (pintype "passive"))
      (node (ref "R54") (pin "2") (pinfunction "2_2") (pintype "passive"))
    )
    (net (code "184") (name "Net-(D55-K)") (class "Default")
      (node (ref "D55") (pin "2") (pinfunction "K_2") (pintype "passive"))
      (node (ref "R55") (pin "2") (pinfunction "2_2") (pintype "passive"))
    )
    (net (code "185") (name "Net-(D56-K)") (class "Default")
      (node (ref "D56") (pin "2") (pinfunction "K_2") (pintype "passive"))
      (node (ref "R56") (pin "2") (pinfunction "2_2") (pintype "passive"))
    )
    (net (code "186") (name "Net-(D57-K)") (class "Default")
      (node (ref "D57") (pin "2") (pinfunction "K_2") (pintype "passive"))
      (node (ref "R57") (pin "2") (pinfunction "2_2") (pintype "passive"))
    )
    (net (code "187") (name "Net-(D58-K)") (class "Default")
      (node (ref "D58") (pin "2") (pinfunction "K_2") (pintype "passive"))
      (node (ref "R58") (pin "2") (pinfunction "2_2") (pintype "passive"))
    )
    (net (code "188") (name "Net-(D59-K)") (class "Default")
      (node (ref "D59") (pin "2") (pinfunction "K_2") (pintype "passive"))
      (node (ref "R59") (pin "2") (pinfunction "2_2") (pintype "passive"))
    )
    (net (code "189") (name "Net-(D60-K)") (class "Default")
      (node (ref "D60") (pin "2") (pinfunction "K_2") (pintype "passive"))
      (node (ref "R60") (pin "2") (pinfunction "2_2") (pintype "passive"))
    )
    (net (code "190") (name "Net-(D61-K)") (class "Default")
      (node (ref "D61") (pin "2") (pinfunction "K_2") (pintype "passive"))
      (node (ref "R61") (pin "2") (pinfunction "2_2") (pintype "passive"))
    )
    (net (code "191") (name "Net-(D62-K)") (class "Default")
      (node (ref "D62") (pin "2") (pinfunction "K_2") (pintype "passive"))
      (node (ref "R62") (pin "2") (pinfunction "2_2") (pintype "passive"))
    )
    (net (code "192") (name "Net-(D63-K)") (class "Default")
      (node (ref "D63") (pin "2") (pinfunction "K_2") (pintype "passive"))
      (node (ref "R63") (pin "2") (pinfunction "2_2") (pintype "passive"))
    )
    (net (code "193") (name "Net-(D64-K)") (class "Default")
      (node (ref "D64") (pin "2") (pinfunction "K_2") (pintype "passive"))
      (node (ref "R64") (pin "2") (pinfunction "2_2") (pintype "passive"))
    )
    (net (code "194") (name "Net-(D65-K)") (class "Default")
      (node (ref "D65") (pin "2") (pinfunction "K_2") (pintype "passive"))
      (node (ref "R65") (pin "2") (pinfunction "2_2") (pintype "passive"))
    )
    (net (code "195") (name "Net-(D66-K)") (class "Default")
      (node (ref "D66") (pin "2") (pinfunction "K_2") (pintype "passive"))
      (node (ref "R66") (pin "2") (pinfunction "2_2") (pintype "passive"))
    )
    (net (code "196") (name "Net-(D67-K)") (class "Default")
      (node (ref "D67") (pin "2") (pinfunction "K_2") (pintype "passive"))
      (node (ref "R67") (pin "2") (pinfunction "2_2") (pintype "passive"))
    )
    (net (code "197") (name "Net-(D68-K)") (class "Default")
      (node (ref "D68") (pin "2") (pinfunction "K_2") (pintype "passive"))
      (node (ref "R68") (pin "2") (pinfunction "2_2") (pintype "passive"))
    )
    (net (code "198") (name "Net-(D69-K)") (class "Default")
      (node (ref "D69") (pin "2") (pinfunction "K_2") (pintype "passive"))
      (node (ref "R69") (pin "2") (pinfunction "2_2") (pintype "passive"))
    )
    (net (code "199") (name "Net-(D70-K)") (class "Default")
      (node (ref "D70") (pin "2") (pinfunction "K_2") (pintype "passive"))
      (node (ref "R70") (pin "2") (pinfunction "2_2") (pintype "passive"))
    )
    (net (code "200") (name "Net-(D71-K)") (class "Default")
      (node (ref "D71") (pin "2") (pinfunction "K_2") (pintype "passive"))
      (node (ref "R71") (pin "2") (pinfunction "2_2") (pintype "passive"))
    )
    (net (code "201") (name "Net-(D72-K)") (class "Default")
      (node (ref "D72") (pin "2") (pinfunction "K_2") (pintype "passive"))
      (node (ref "R72") (pin "2") (pinfunction "2_2") (pintype "passive"))
    )
    (net (code "202") (name "unconnected-(RL37-Pad4)") (class "Default")
      (node (ref "RL37") (pin "4") (pintype "passive"))
    )
    (net (code "203") (name "unconnected-(RL37-Pad5)") (class "Default")
      (node (ref "RL37") (pin "5") (pintype "passive"))
    )
    (net (code "204") (name "unconnected-(RL37-Pad6)") (class "Default")
      (node (ref "RL37") (pin "6") (pintype "passive"))
    )
    (net (code "205") (name "unconnected-(RL38-Pad4)") (class "Default")
      (node (ref "RL38") (pin "4") (pintype "passive"))
    )
    (net (code "206") (name "unconnected-(RL38-Pad5)") (class "Default")
      (node (ref "RL38") (pin "5") (pintype "passive"))
    )
    (net (code "207") (name "unconnected-(RL38-Pad6)") (class "Default")
      (node (ref "RL38") (pin "6") (pintype "passive"))
    )
    (net (code "208") (name "unconnected-(RL39-Pad4)") (class "Default")
      (node (ref "RL39") (pin "4") (pintype "passive"))
    )
    (net (code "209") (name "unconnected-(RL39-Pad5)") (class "Default")
      (node (ref "RL39") (pin "5") (pintype "passive"))
    )
    (net (code "210") (name "unconnected-(RL39-Pad6)") (class "Default")
      (node (ref "RL39") (pin "6") (pintype "passive"))
    )
    (net (code "211") (name "unconnected-(RL40-Pad4)") (class "Default")
      (node (ref "RL40") (pin "4") (pintype "passive"))
    )
    (net (code "212") (name "unconnected-(RL40-Pad5)") (class "Default")
      (node (ref "RL40") (pin "5") (pintype "passive"))
    )
    (net (code "213") (name "unconnected-(RL40-Pad6)") (class "Default")
      (node (ref "RL40") (pin "6") (pintype "passive"))
    )
    (net (code "214") (name "unconnected-(RL41-Pad4)") (class "Default")
      (node (ref "RL41") (pin "4") (pintype "passive"))
    )
    (net (code "215") (name "unconnected-(RL41-Pad5)") (class "Default")
      (node (ref "RL41") (pin "5") (pintype "passive"))
    )
    (net (code "216") (name "unconnected-(RL41-Pad6)") (class "Default")
      (node (ref "RL41") (pin "6") (pintype "passive"))
    )
    (net (code "217") (name "unconnected-(RL42-Pad4)") (class "Default")
      (node (ref "RL42") (pin "4") (pintype "passive"))
    )
    (net (code "218") (name "unconnected-(RL42-Pad5)") (class "Default")
      (node (ref "RL42") (pin "5") (pintype "passive"))
    )
    (net (code "219") (name "unconnected-(RL42-Pad6)") (class "Default")
      (node (ref "RL42") (pin "6") (pintype "passive"))
    )
    (net (code "220") (name "unconnected-(RL43-Pad4)") (class "Default")
      (node (ref "RL43") (pin "4") (pintype "passive"))
    )
    (net (code "221") (name "unconnected-(RL43-Pad5)") (class "Default")
      (node (ref "RL43") (pin "5") (pintype "passive"))
    )
    (net (code "222") (name "unconnected-(RL43-Pad6)") (class "Default")
      (node (ref "RL43") (pin "6") (pintype "passive"))
    )
    (net (code "223") (name "unconnected-(RL44-Pad4)") (class "Default")
      (node (ref "RL44") (pin "4") (pintype "passive"))
    )
    (net (code "224") (name "unconnected-(RL44-Pad5)") (class "Default")
      (node (ref "RL44") (pin "5") (pintype "passive"))
    )
    (net (code "225") (name "unconnected-(RL44-Pad6)") (class "Default")
      (node (ref "RL44") (pin "6") (pintype "passive"))
    )
    (net (code "226") (name "unconnected-(RL45-Pad4)") (class "Default")
      (node (ref "RL45") (pin "4") (pintype "passive"))
    )
    (net (code "227") (name "unconnected-(RL45-Pad5)") (class "Default")
      (node (ref "RL45") (pin "5") (pintype "passive"))
    )
    (net (code "228") (name "unconnected-(RL45-Pad6)") (class "Default")
      (node (ref "RL45") (pin "6") (pintype "passive"))
    )
    (net (code "229") (name "unconnected-(RL46-Pad4)") (class "Default")
      (node (ref "RL46") (pin "4") (pintype "passive"))
    )
    (net (code "230") (name "unconnected-(RL46-Pad5)") (class "Default")
      (node (ref "RL46") (pin "5") (pintype "passive"))
    )
    (net (code "231") (name "unconnected-(RL46-Pad6)") (class "Default")
      (node (ref "RL46") (pin "6") (pintype "passive"))
    )
    (net (code "232") (name "unconnected-(RL47-Pad4)") (class "Default")
      (node (ref "RL47") (pin "4") (pintype "passive"))
    )
    (net (code "233") (name "unconnected-(RL47-Pad5)") (class "Default")
      (node (ref "RL47") (pin "5") (pintype "passive"))
    )
    (net (code "234") (name "unconnected-(RL47-Pad6)") (class "Default")
      (node (ref "RL47") (pin "6") (pintype "passive"))
    )
    (net (code "235") (name "unconnected-(RL48-Pad4)") (class "Default")
      (node (ref "RL48") (pin "4") (pintype "passive"))
    )
    (net (code "236") (name "unconnected-(RL48-Pad5)") (class "Default")
      (node (ref "RL48") (pin "5") (pintype "passive"))
    )
    (net (code "237") (name "unconnected-(RL48-Pad6)") (class "Default")
      (node (ref "RL48") (pin "6") (pintype "passive"))
    )
    (net (code "238") (name "unconnected-(RL49-Pad4)") (class "Default")
      (node (ref "RL49") (pin "4") (pintype "passive"))
    )
    (net (code "239") (name "unconnected-(RL49-Pad5)") (class "Default")
      (node (ref "RL49") (pin "5") (pintype "passive"))
    )
    (net (code "240") (name "unconnected-(RL49-Pad6)") (class "Default")
      (node (ref "RL49") (pin "6") (pintype "passive"))
    )
    (net (code "241") (name "unconnected-(RL50-Pad4)") (class "Default")
      (node (ref "RL50") (pin "4") (pintype "passive"))
    )
    (net (code "242") (name "unconnected-(RL50-Pad5)") (class "Default")
      (node (ref "RL50") (pin "5") (pintype "passive"))
    )
    (net (code "243") (name "unconnected-(RL50-Pad6)") (class "Default")
      (node (ref "RL50") (pin "6") (pintype "passive"))
    )
    (net (code "244") (name "unconnected-(RL51-Pad4)") (class "Default")
      (node (ref "RL51") (pin "4") (pintype "passive"))
    )
    (net (code "245") (name "unconnected-(RL51-Pad5)") (class "Default")
      (node (ref "RL51") (pin "5") (pintype "passive"))
    )
    (net (code "246") (name "unconnected-(RL51-Pad6)") (class "Default")
      (node (ref "RL51") (pin "6") (pintype "passive"))
    )
    (net (code "247") (name "unconnected-(RL52-Pad4)") (class "Default")
      (node (ref "RL52") (pin "4") (pintype "passive"))
    )
    (net (code "248") (name "unconnected-(RL52-Pad5)") (class "Default")
      (node (ref "RL52") (pin "5") (pintype "passive"))
    )
    (net (code "249") (name "unconnected-(RL52-Pad6)") (class "Default")
      (node (ref "RL52") (pin "6") (pintype "passive"))
    )
    (net (code "250") (name "unconnected-(RL53-Pad4)") (class "Default")
      (node (ref "RL53") (pin "4") (pintype "passive"))
    )
    (net (code "251") (name "unconnected-(RL53-Pad5)") (class "Default")
      (node (ref "RL53") (pin "5") (pintype "passive"))
    )
    (net (code "252") (name "unconnected-(RL53-Pad6)") (class "Default")
      (node (ref "RL53") (pin "6") (pintype "passive"))
    )
    (net (code "253") (name "unconnected-(RL54-Pad4)") (class "Default")
      (node (ref "RL54") (pin "4") (pintype "passive"))
    )
    (net (code "254") (name "unconnected-(RL54-Pad5)") (class "Default")
      (node (ref "RL54") (pin "5") (pintype "passive"))
    )
    (net (code "255") (name "unconnected-(RL54-Pad6)") (class "Default")
      (node (ref "RL54") (pin "6") (pintype "passive"))
    )
    (net (code "256") (name "unconnected-(RL55-Pad4)") (class "Default")
      (node (ref "RL55") (pin "4") (pintype "passive"))
    )
    (net (code "257") (name "unconnected-(RL55-Pad5)") (class "Default")
      (node (ref "RL55") (pin "5") (pintype "passive"))
    )
    (net (code "258") (name "unconnected-(RL55-Pad6)") (class "Default")
      (node (ref "RL55") (pin "6") (pintype "passive"))
    )
    (net (code "259") (name "unconnected-(RL56-Pad4)") (class "Default")
      (node (ref "RL56") (pin "4") (pintype "passive"))
    )
    (net (code "260") (name "unconnected-(RL56-Pad5)") (class "Default")
      (node (ref "RL56") (pin "5") (pintype "passive"))
    )
    (net (code "261") (name "unconnected-(RL56-Pad6)") (class "Default")
      (node (ref "RL56") (pin "6") (pintype "passive"))
    )
    (net (code "262") (name "unconnected-(RL57-Pad4)") (class "Default")
      (node (ref "RL57") (pin "4") (pintype "passive"))
    )
    (net (code "263") (name "unconnected-(RL57-Pad5)") (class "Default")
      (node (ref "RL57") (pin "5") (pintype "passive"))
    )
    (net (code "264") (name "unconnected-(RL57-Pad6)") (class "Default")
      (node (ref "RL57") (pin "6") (pintype "passive"))
    )
    (net (code "265") (name "unconnected-(RL58-Pad4)") (class "Default")
      (node (ref "RL58") (pin "4") (pintype "passive"))
    )
    (net (code "266") (name "unconnected-(RL58-Pad5)") (class "Default")
      (node (ref "RL58") (pin "5") (pintype "passive"))
    )
    (net (code "267") (name "unconnected-(RL58-Pad6)") (class "Default")
      (node (ref "RL58") (pin "6") (pintype "passive"))
    )
    (net (code "268") (name "unconnected-(RL59-Pad4)") (class "Default")
      (node (ref "RL59") (pin "4") (pintype "passive"))
    )
    (net (code "269") (name "unconnected-(RL59-Pad5)") (class "Default")
      (node (ref "RL59") (pin "5") (pintype "passive"))
    )
    (net (code "270") (name "unconnected-(RL59-Pad6)") (class "Default")
      (node (ref "RL59") (pin "6") (pintype "passive"))
    )
    (net (code "271") (name "unconnected-(RL60-Pad4)") (class "Default")
      (node (ref "RL60") (pin "4") (pintype "passive"))
    )
    (net (code "272") (name "unconnected-(RL60-Pad5)") (class "Default")
      (node (ref "RL60") (pin "5") (pintype "passive"))
    )
    (net (code "273") (name "unconnected-(RL60-Pad6)") (class "Default")
      (node (ref "RL60") (pin "6") (pintype "passive"))
    )
    (net (code "274") (name "unconnected-(RL61-Pad4)") (class "Default")
      (node (ref "RL61") (pin "4") (pintype "passive"))
    )
    (net (code "275") (name "unconnected-(RL61-Pad5)") (class "Default")
      (node (ref "RL61") (pin "5") (pintype "passive"))
    )
    (net (code "276") (name "unconnected-(RL61-Pad6)") (class "Default")
      (node (ref "RL61") (pin "6") (pintype "passive"))
    )
    (net (code "277") (name "unconnected-(RL62-Pad4)") (class "Default")
      (node (ref "RL62") (pin "4") (pintype "passive"))
    )
    (net (code "278") (name "unconnected-(RL62-Pad5)") (class "Default")
      (node (ref "RL62") (pin "5") (pintype "passive"))
    )
    (net (code "279") (name "unconnected-(RL62-Pad6)") (class "Default")
      (node (ref "RL62") (pin "6") (pintype "passive"))
    )
    (net (code "280") (name "unconnected-(RL63-Pad4)") (class "Default")
      (node (ref "RL63") (pin "4") (pintype "passive"))
    )
    (net (code "281") (name "unconnected-(RL63-Pad5)") (class "Default")
      (node (ref "RL63") (pin "5") (pintype "passive"))
    )
    (net (code "282") (name "unconnected-(RL63-Pad6)") (class "Default")
      (node (ref "RL63") (pin "6") (pintype "passive"))
    )
    (net (code "283") (name "unconnected-(RL64-Pad4)") (class "Default")
      (node (ref "RL64") (pin "4") (pintype "passive"))
    )
    (net (code "284") (name "unconnected-(RL64-Pad5)") (class "Default")
      (node (ref "RL64") (pin "5") (pintype "passive"))
    )
    (net (code "285") (name "unconnected-(RL64-Pad6)") (class "Default")
      (node (ref "RL64") (pin "6") (pintype "passive"))
    )
    (net (code "286") (name "unconnected-(RL65-Pad4)") (class "Default")
      (node (ref "RL65") (pin "4") (pintype "passive"))
    )
    (net (code "287") (name "unconnected-(RL65-Pad5)") (class "Default")
      (node (ref "RL65") (pin "5") (pintype "passive"))
    )
    (net (code "288") (name "unconnected-(RL65-Pad6)") (class "Default")
      (node (ref "RL65") (pin "6") (pintype "passive"))
    )
    (net (code "289") (name "unconnected-(RL66-Pad4)") (class "Default")
      (node (ref "RL66") (pin "4") (pintype "passive"))
    )
    (net (code "290") (name "unconnected-(RL66-Pad5)") (class "Default")
      (node (ref "RL66") (pin "5") (pintype "passive"))
    )
    (net (code "291") (name "unconnected-(RL66-Pad6)") (class "Default")
      (node (ref "RL66") (pin "6") (pintype "passive"))
    )
    (net (code "292") (name "unconnected-(RL67-Pad4)") (class "Default")
      (node (ref "RL67") (pin "4") (pintype "passive"))
    )
    (net (code "293") (name "unconnected-(RL67-Pad5)") (class "Default")
      (node (ref "RL67") (pin "5") (pintype "passive"))
    )
    (net (code "294") (name "unconnected-(RL67-Pad6)") (class "Default")
      (node (ref "RL67") (pin "6") (pintype "passive"))
    )
    (net (code "295") (name "unconnected-(RL68-Pad4)") (class "Default")
      (node (ref "RL68") (pin "4") (pintype "passive"))
    )
    (net (code "296") (name "unconnected-(RL68-Pad5)") (class "Default")
      (node (ref "RL68") (pin "5") (pintype "passive"))
    )
    (net (code "297") (name "unconnected-(RL68-Pad6)") (class "Default")
      (node (ref "RL68") (pin "6") (pintype "passive"))
    )
    (net (code "298") (name "unconnected-(RL69-Pad4)") (class "Default")
      (node (ref "RL69") (pin "4") (pintype "passive"))
    )
    (net (code "299") (name "unconnected-(RL69-Pad5)") (class "Default")
      (node (ref "RL69") (pin "5") (pintype "passive"))
    )
    (net (code "300") (name "unconnected-(RL69-Pad6)") (class "Default")
      (node (ref "RL69") (pin "6") (pintype "passive"))
    )
    (net (code "301") (name "unconnected-(RL70-Pad4)") (class "Default")
      (node (ref "RL70") (pin "4") (pintype "passive"))
    )
    (net (code "302") (name "unconnected-(RL70-Pad5)") (class "Default")
      (node (ref "RL70") (pin "5") (pintype "passive"))
    )
    (net (code "303") (name "unconnected-(RL70-Pad6)") (class "Default")
      (node (ref "RL70") (pin "6") (pintype "passive"))
    )
    (net (code "304") (name "unconnected-(RL71-Pad4)") (class "Default")
      (node (ref "RL71") (pin "4") (pintype "passive"))
    )
    (net (code "305") (name "unconnected-(RL71-Pad5)") (class "Default")
      (node (ref "RL71") (pin "5") (pintype "passive"))
    )
    (net (code "306") (name "unconnected-(RL71-Pad6)") (class "Default")
      (node (ref "RL71") (pin "6") (pintype "passive"))
    )
    (net (code "307") (name "unconnected-(RL72-Pad4)") (class "Default")
      (node (ref "RL72") (pin "4") (pintype "passive"))
    )
    (net (code "308") (name "unconnected-(RL72-Pad5)") (class "Default")
      (node (ref "RL72") (pin "5") (pintype "passive"))
    )
    (net (code "309") (name "unconnected-(RL72-Pad6)") (class "Default")
      (node (ref "RL72") (pin "6") (pintype "passive"))
    )
  )
)
